# power-slot.net
KiCad netlist of a schematic drawn in EAGLE
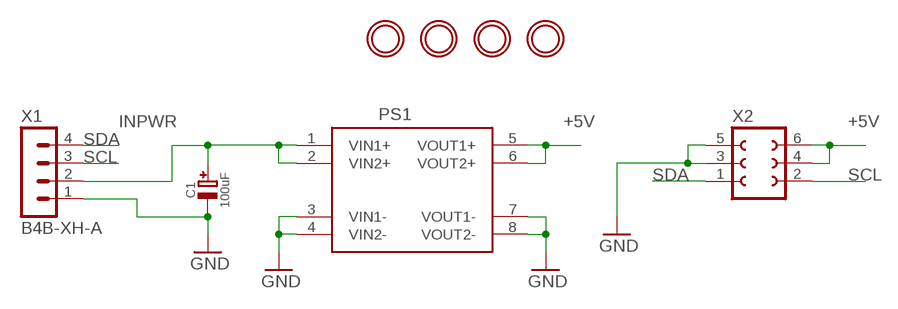
[diagram p0: schematic, sheet 1]

(export (version "E")
  (design (tool "Eeschema 10.0.6"))
  (components
    (comp (ref "C1")
      (value "100uF")
      (footprint "eagle-import:CELEC_3.5MM_8MM")
      (libsource (lib "eagle-import") (part "CAP_ELECTROLYTICPTH_3.5MMGRID_8MMDIA"))
    )
    (comp (ref "PS1")
      (value "K8801MODULE")
      (footprint "eagle-import:K8801")
      (libsource (lib "eagle-import") (part "K8801MODULE"))
    )
    (comp (ref "U$1")
      (value "MOUNTINGHOLE2.7THIN")
      (footprint "eagle-import:MOUNTINGHOLE_2.7_PLATEDTHIN")
      (libsource (lib "eagle-import") (part "MOUNTINGHOLE2.7THIN"))
    )
    (comp (ref "U$2")
      (value "MOUNTINGHOLE2.7THIN")
      (footprint "eagle-import:MOUNTINGHOLE_2.7_PLATEDTHIN")
      (libsource (lib "eagle-import") (part "MOUNTINGHOLE2.7THIN"))
    )
    (comp (ref "U$3")
      (value "MOUNTINGHOLE2.7THIN")
      (footprint "eagle-import:MOUNTINGHOLE_2.7_PLATEDTHIN")
      (libsource (lib "eagle-import") (part "MOUNTINGHOLE2.7THIN"))
    )
    (comp (ref "U$4")
      (value "MOUNTINGHOLE2.7THIN")
      (footprint "eagle-import:MOUNTINGHOLE_2.7_PLATEDTHIN")
      (libsource (lib "eagle-import") (part "MOUNTINGHOLE2.7THIN"))
    )
    (comp (ref "X1")
      (value "B4B-XH-A")
      (footprint "eagle-import:B4B-XH-A")
      (libsource (lib "eagle-import") (part "B4B-XH-A"))
    )
    (comp (ref "X2")
      (value "CON-FE03-2CARDEDGE-0.1")
      (footprint "eagle-import:FE3-2-CARDEDGE-0.1")
      (libsource (lib "eagle-import") (part "CON-FE03-2CARDEDGE-0.1"))
    )
  )
  (nets
    (net (code "1") (name "/+5V") (class "Default")
      (node (ref "PS1") (pin "5") (pinfunction "VOUT1+_5") (pintype "bidirectional"))
      (node (ref "PS1") (pin "6") (pinfunction "VOUT2+_6") (pintype "bidirectional"))
      (node (ref "X2") (pin "4") (pinfunction "4_4") (pintype "passive"))
      (node (ref "X2") (pin "6") (pinfunction "6_6") (pintype "passive"))
    )
    (net (code "2") (name "/INPWR") (class "Default")
      (node (ref "C1") (pin "+") (pinfunction "+_+") (pintype "passive"))
      (node (ref "PS1") (pin "1") (pinfunction "VIN1+_1") (pintype "bidirectional"))
      (node (ref "PS1") (pin "2") (pinfunction "VIN2+_2") (pintype "bidirectional"))
      (node (ref "X1") (pin "2") (pinfunction "2_2") (pintype "passive"))
    )
    (net (code "3") (name "/SCL") (class "Default")
      (node (ref "X1") (pin "3") (pinfunction "3_3") (pintype "passive"))
      (node (ref "X2") (pin "2") (pinfunction "2_2") (pintype "passive"))
    )
    (net (code "4") (name "/SDA") (class "Default")
      (node (ref "X1") (pin "4") (pinfunction "4_4") (pintype "passive"))
      (node (ref "X2") (pin "1") (pinfunction "1_1") (pintype "passive"))
    )
    (net (code "5") (name "GND") (class "Default")
      (node (ref "C1") (pin "-") (pinfunction "-_-") (pintype "passive"))
      (node (ref "PS1") (pin "3") (pinfunction "VIN1-_3") (pintype "bidirectional"))
      (node (ref "PS1") (pin "4") (pinfunction "VIN2-_4") (pintype "bidirectional"))
      (node (ref "PS1") (pin "7") (pinfunction "VOUT1-_7") (pintype "bidirectional"))
      (node (ref "PS1") (pin "8") (pinfunction "VOUT2-_8") (pintype "bidirectional"))
      (node (ref "X1") (pin "1") (pinfunction "1_1") (pintype "passive"))
      (node (ref "X2") (pin "3") (pinfunction "3_3") (pintype "passive"))
      (node (ref "X2") (pin "5") (pinfunction "5_5") (pintype "passive"))
    )
  )
)
